# EEZ_AUX_PS_r4B40.net
KiCad netlist of a schematic drawn in EAGLE
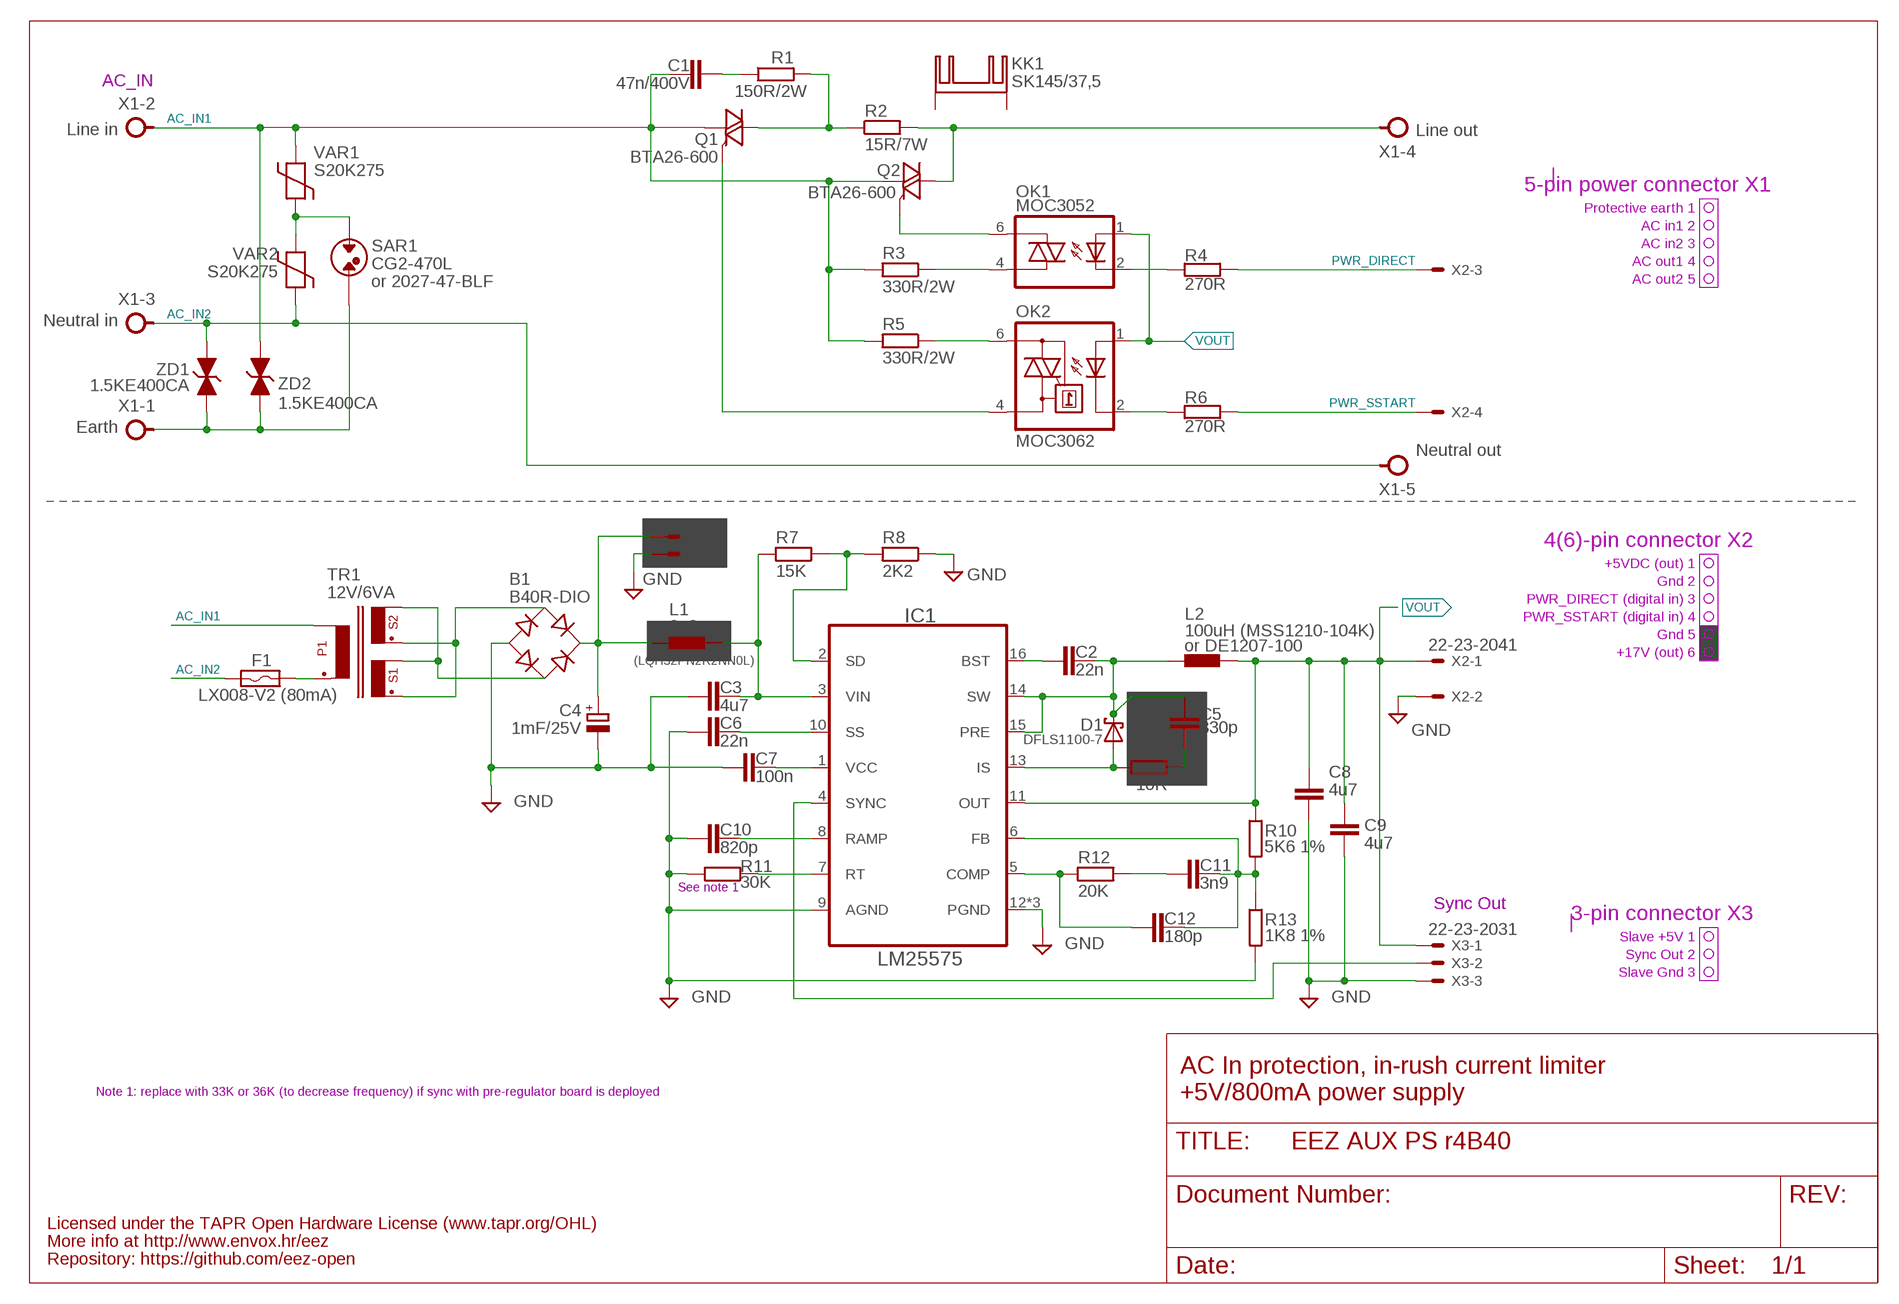
[diagram p0: schematic, sheet 1]

(export (version "E")
  (design (tool "Eeschema 10.0.6"))
  (components
    (comp (ref "B1")
      (value "B40R-DIO")
      (footprint "eagle-import:RB1A")
      (libsource (lib "eagle-import") (part "RECTIFIER-RB1A"))
    )
    (comp (ref "C1")
      (value "47n/400V")
      (footprint "eagle-import:C075-052X106")
      (libsource (lib "eagle-import") (part "C-EU075-052X106"))
    )
    (comp (ref "C2")
      (value "22n")
      (footprint "eagle-import:C0805")
      (libsource (lib "eagle-import") (part "C-EUC0805"))
    )
    (comp (ref "C3")
      (value "4u7")
      (footprint "eagle-import:C1210")
      (libsource (lib "eagle-import") (part "C-EUC1210"))
    )
    (comp (ref "C4")
      (value "1mF/25V")
      (footprint "eagle-import:ECAP5_10.5")
      (libsource (lib "eagle-import") (part "ECAP5G_10.5MM"))
    )
    (comp (ref "C5")
      (value "330p")
      (footprint "eagle-import:C0805")
      (libsource (lib "eagle-import") (part "C-EUC0805"))
    )
    (comp (ref "C6")
      (value "22n")
      (footprint "eagle-import:C0805")
      (libsource (lib "eagle-import") (part "C-EUC0805"))
    )
    (comp (ref "C7")
      (value "100n")
      (footprint "eagle-import:C0805")
      (libsource (lib "eagle-import") (part "C-EUC0805"))
    )
    (comp (ref "C8")
      (value "4u7")
      (footprint "eagle-import:C1210")
      (libsource (lib "eagle-import") (part "C-EUC1210"))
    )
    (comp (ref "C9")
      (value "4u7")
      (footprint "eagle-import:C1210")
      (libsource (lib "eagle-import") (part "C-EUC1210"))
    )
    (comp (ref "C10")
      (value "820p")
      (footprint "eagle-import:C0805")
      (libsource (lib "eagle-import") (part "C-EUC0805"))
    )
    (comp (ref "C11")
      (value "3n9")
      (footprint "eagle-import:C0805")
      (libsource (lib "eagle-import") (part "C-EUC0805"))
    )
    (comp (ref "C12")
      (value "180p")
      (footprint "eagle-import:C0805")
      (libsource (lib "eagle-import") (part "C-EUC0805"))
    )
    (comp (ref "D1")
      (value "DFLS1100-7")
      (footprint "eagle-import:SOD123")
      (libsource (lib "eagle-import") (part "SCHOTTKYSOD123"))
    )
    (comp (ref "F1")
      (value "LX008-V2 (80mA)")
      (footprint "eagle-import:POLYSWITCH-R7")
      (libsource (lib "eagle-import") (part "FUSE_RESETTABLER7"))
    )
    (comp (ref "IC1")
      (value "LM25575")
      (footprint "eagle-import:SOP65P640X110-17N_HOLE")
      (libsource (lib "eagle-import") (part "LM(2)5575"))
    )
    (comp (ref "KK1")
      (value "SK145/37,5")
      (footprint "eagle-import:SK145")
      (libsource (lib "eagle-import") (part "SK145"))
    )
    (comp (ref "L1")
      (value "2u2")
      (footprint "eagle-import:L1210")
      (libsource (lib "eagle-import") (part "L1210"))
    )
    (comp (ref "L2")
      (value "100uH (MSS1210-104K)")
      (footprint "eagle-import:MSS1278")
      (libsource (lib "eagle-import") (part "COILCRAFT_MSS1278"))
    )
    (comp (ref "OK1")
      (value "MOC3052")
      (footprint "eagle-import:DIL6-SMD")
      (libsource (lib "eagle-import") (part "MOC305X"))
    )
    (comp (ref "OK2")
      (value "MOC3062")
      (footprint "eagle-import:DIL6-SMD")
      (fields
        (field (name "MF") "FAIRCHILD SEMICONDUCTOR")
        (field (name "MPN") "MOC3033S-M")
        (field (name "MF_1") "FAIRCHILD SEMICONDUCTOR")
        (field (name "MPN_1") "MOC3033S-M")
        (field (name "OC_FARNELL") "unknown")
        (field (name "OC_NEWARK") "05C2878")
      )
      (libsource (lib "eagle-import") (part "MOC30S33"))
    )
    (comp (ref "Q1")
      (value "BTA26-600")
      (footprint "eagle-import:TOP3S-1")
      (libsource (lib "eagle-import") (part "BTA26-V"))
    )
    (comp (ref "Q2")
      (value "BTA26-600")
      (footprint "eagle-import:TOP3S-1")
      (libsource (lib "eagle-import") (part "BTA26-V"))
    )
    (comp (ref "R1")
      (value "150R/2W")
      (footprint "eagle-import:R2512")
      (libsource (lib "eagle-import") (part "R-EU_R2512"))
    )
    (comp (ref "R2")
      (value "15R/7W")
      (footprint "eagle-import:R_0913")
      (libsource (lib "eagle-import") (part "R_EU7W"))
    )
    (comp (ref "R3")
      (value "330R/2W")
      (footprint "eagle-import:R2512")
      (libsource (lib "eagle-import") (part "R-EU_R2512"))
    )
    (comp (ref "R4")
      (value "270R")
      (footprint "eagle-import:R0805")
      (libsource (lib "eagle-import") (part "R-EU_R0805"))
    )
    (comp (ref "R5")
      (value "330R/2W")
      (footprint "eagle-import:R2512")
      (libsource (lib "eagle-import") (part "R-EU_R2512"))
    )
    (comp (ref "R6")
      (value "270R")
      (footprint "eagle-import:R0805")
      (libsource (lib "eagle-import") (part "R-EU_R0805"))
    )
    (comp (ref "R7")
      (value "15K")
      (footprint "eagle-import:R0805")
      (libsource (lib "eagle-import") (part "R-EU_R0805"))
    )
    (comp (ref "R8")
      (value "2K2")
      (footprint "eagle-import:R0805")
      (libsource (lib "eagle-import") (part "R-EU_R0805"))
    )
    (comp (ref "R9")
      (value "10R")
      (footprint "eagle-import:R1206")
      (libsource (lib "eagle-import") (part "R-EU_R1206"))
    )
    (comp (ref "R10")
      (value "5K6 1%")
      (footprint "eagle-import:R0805")
      (libsource (lib "eagle-import") (part "R-EU_R0805"))
    )
    (comp (ref "R11")
      (value "30K")
      (footprint "eagle-import:R0805")
      (libsource (lib "eagle-import") (part "R-EU_R0805"))
    )
    (comp (ref "R12")
      (value "20K")
      (footprint "eagle-import:R0805")
      (libsource (lib "eagle-import") (part "R-EU_R0805"))
    )
    (comp (ref "R13")
      (value "1K8 1%")
      (footprint "eagle-import:R0805")
      (libsource (lib "eagle-import") (part "R-EU_R0805"))
    )
    (comp (ref "SAR1")
      (value "CG2-470L")
      (footprint "eagle-import:SAR")
      (libsource (lib "eagle-import") (part "SAR"))
    )
    (comp (ref "TR1")
      (value "12V/6VA")
      (footprint "eagle-import:PCB_TRAFO6VA_DUAL")
      (libsource (lib "eagle-import") (part "PCB_TRAFO6VACOMBO"))
    )
    (comp (ref "VAR1")
      (value "S20K275")
      (footprint "eagle-import:VARISTOR")
      (libsource (lib "eagle-import") (part "VARISTOR"))
    )
    (comp (ref "VAR2")
      (value "S20K275")
      (footprint "eagle-import:VARISTOR")
      (libsource (lib "eagle-import") (part "VARISTOR"))
    )
    (comp (ref "X1")
      (value "AC_IN")
      (footprint "eagle-import:TBLOCK5.0_5")
      (libsource (lib "eagle-import") (part "TBLOCK5.0_5A"))
    )
    (comp (ref "X2")
      (value "22-23-2041")
      (footprint "eagle-import:22-23-2061")
      (fields
        (field (name "MF") "MOLEX")
        (field (name "MPN") "22-23-2061")
        (field (name "MPN_1") "22-23-2061")
        (field (name "OC_FARNELL") "1462922")
        (field (name "OC_NEWARK") "27C1933")
      )
      (libsource (lib "eagle-import") (part "22-23-2061"))
    )
    (comp (ref "X3")
      (value "22-23-2031")
      (footprint "eagle-import:22-23-2031")
      (fields (field (name "MF") "MOLEX"))
      (libsource (lib "eagle-import") (part "22-23-2031"))
    )
    (comp (ref "ZD1")
      (value "1.5KE400CA")
      (footprint "eagle-import:DO201-BIDIR")
      (libsource (lib "eagle-import") (part "1.5KE-BIDIR"))
    )
    (comp (ref "ZD2")
      (value "1.5KE400CA")
      (footprint "eagle-import:DO201-BIDIR")
      (libsource (lib "eagle-import") (part "1.5KE-BIDIR"))
    )
  )
  (nets
    (net (code "1") (name "/AC_IN1") (class "Default")
      (node (ref "C1") (pin "2") (pinfunction "2_2") (pintype "passive"))
      (node (ref "Q1") (pin "A1") (pinfunction "A1_A1") (pintype "passive"))
      (node (ref "Q2") (pin "A1") (pinfunction "A1_A1") (pintype "passive"))
      (node (ref "R3") (pin "2") (pinfunction "2_2") (pintype "passive"))
      (node (ref "R5") (pin "2") (pinfunction "2_2") (pintype "passive"))
      (node (ref "TR1") (pin "NC1") (pinfunction "P1_NC1") (pintype "passive"))
      (node (ref "TR1") (pin "P1") (pinfunction "P1_P1") (pintype "passive"))
      (node (ref "TR1") (pin "P1.1") (pinfunction "P1_P1.1") (pintype "passive"))
      (node (ref "TR1") (pin "P1.2") (pinfunction "P1_P1.2") (pintype "passive"))
      (node (ref "VAR1") (pin "P$2") (pinfunction "P$2_P$2") (pintype "bidirectional"))
      (node (ref "X1") (pin "2") (pinfunction "1_2") (pintype "bidirectional"))
      (node (ref "ZD2") (pin "A") (pinfunction "2_A") (pintype "passive"))
    )
    (net (code "2") (name "/AC_IN2") (class "Default")
      (node (ref "F1") (pin "P$1") (pinfunction "1_P$1") (pintype "passive"))
      (node (ref "VAR2") (pin "P$1") (pinfunction "P$1_P$1") (pintype "bidirectional"))
      (node (ref "X1") (pin "3") (pinfunction "1_3") (pintype "bidirectional"))
      (node (ref "X1") (pin "5") (pinfunction "1_5") (pintype "bidirectional"))
      (node (ref "ZD1") (pin "A") (pinfunction "2_A") (pintype "passive"))
    )
    (net (code "3") (name "/PWR_DIRECT") (class "Default")
      (node (ref "R4") (pin "2") (pinfunction "2_2") (pintype "passive"))
      (node (ref "X2") (pin "3") (pinfunction "S_3") (pintype "passive"))
    )
    (net (code "4") (name "/PWR_SSTART") (class "Default")
      (node (ref "R6") (pin "2") (pinfunction "2_2") (pintype "passive"))
      (node (ref "X2") (pin "4") (pinfunction "S_4") (pintype "passive"))
    )
    (net (code "5") (name "GND") (class "Default")
      (node (ref "B1") (pin "-") (pinfunction "-_-") (pintype "passive"))
      (node (ref "C10") (pin "1") (pinfunction "1_1") (pintype "passive"))
      (node (ref "C3") (pin "2") (pinfunction "2_2") (pintype "passive"))
      (node (ref "C4") (pin "-") (pinfunction "-_-") (pintype "passive"))
      (node (ref "C6") (pin "2") (pinfunction "2_2") (pintype "passive"))
      (node (ref "C7") (pin "1") (pinfunction "1_1") (pintype "passive"))
      (node (ref "C8") (pin "2") (pinfunction "2_2") (pintype "passive"))
      (node (ref "C9") (pin "2") (pinfunction "2_2") (pintype "passive"))
      (node (ref "IC1") (pin "12") (pinfunction "PGND_12") (pintype "passive"))
      (node (ref "IC1") (pin "9") (pinfunction "AGND_9") (pintype "passive"))
      (node (ref "IC1") (pin "TP") (pinfunction "PGND_TP") (pintype "passive"))
      (node (ref "IC1") (pin "TP2") (pinfunction "PGND_TP2") (pintype "passive"))
      (node (ref "R11") (pin "2") (pinfunction "2_2") (pintype "passive"))
      (node (ref "R13") (pin "2") (pinfunction "2_2") (pintype "passive"))
      (node (ref "R8") (pin "1") (pinfunction "1_1") (pintype "passive"))
      (node (ref "X2") (pin "2") (pinfunction "S_2") (pintype "passive"))
      (node (ref "X2") (pin "5") (pinfunction "S_5") (pintype "passive"))
      (node (ref "X3") (pin "3") (pinfunction "S_3") (pintype "passive"))
    )
    (net (code "6") (name "Net-(B1-PadAC1)") (class "Default")
      (node (ref "B1") (pin "AC1") (pinfunction "AC1_AC1") (pintype "passive"))
      (node (ref "TR1") (pin "S1.1") (pinfunction "S1.1_S1.1") (pintype "passive"))
      (node (ref "TR1") (pin "S2.1") (pinfunction "S2.1_S2.1") (pintype "passive"))
      (node (ref "TR1") (pin "S2.1A") (pinfunction "S2.1_S2.1A") (pintype "passive"))
    )
    (net (code "7") (name "Net-(B1-PadAC2)") (class "Default")
      (node (ref "B1") (pin "AC2") (pinfunction "AC2_AC2") (pintype "passive"))
      (node (ref "TR1") (pin "S1.2") (pinfunction "S1.2_S1.2") (pintype "passive"))
      (node (ref "TR1") (pin "S1.2A") (pinfunction "S1.2_S1.2A") (pintype "passive"))
      (node (ref "TR1") (pin "S1.2NC") (pinfunction "S1.2_S1.2NC") (pintype "passive"))
      (node (ref "TR1") (pin "S2.2") (pinfunction "S2.2_S2.2") (pintype "passive"))
    )
    (net (code "8") (name "Net-(C1-Pad1)") (class "Default")
      (node (ref "C1") (pin "1") (pinfunction "1_1") (pintype "passive"))
      (node (ref "R1") (pin "1") (pinfunction "1_1") (pintype "passive"))
    )
    (net (code "9") (name "Net-(C5-Pad2)") (class "Default")
      (node (ref "C5") (pin "2") (pinfunction "2_2") (pintype "passive"))
      (node (ref "R9") (pin "2") (pinfunction "2_2") (pintype "passive"))
    )
    (net (code "10") (name "Net-(C11-Pad2)") (class "Default")
      (node (ref "C11") (pin "2") (pinfunction "2_2") (pintype "passive"))
      (node (ref "R12") (pin "2") (pinfunction "2_2") (pintype "passive"))
    )
    (net (code "11") (name "Net-(F1-2)") (class "Default")
      (node (ref "F1") (pin "P$2") (pinfunction "2_P$2") (pintype "passive"))
      (node (ref "TR1") (pin "P2") (pinfunction "P2_P2") (pintype "passive"))
      (node (ref "TR1") (pin "P2.1") (pinfunction "P2_P2.1") (pintype "passive"))
      (node (ref "TR1") (pin "P2.2") (pinfunction "P2_P2.2") (pintype "passive"))
    )
    (net (code "12") (name "Net-(IC1-BST)") (class "Default")
      (node (ref "C2") (pin "2") (pinfunction "2_2") (pintype "passive"))
      (node (ref "IC1") (pin "16") (pinfunction "BST_16") (pintype "input"))
    )
    (net (code "13") (name "Net-(IC1-COMP)") (class "Default")
      (node (ref "C12") (pin "2") (pinfunction "2_2") (pintype "passive"))
      (node (ref "IC1") (pin "5") (pinfunction "COMP_5") (pintype "input"))
      (node (ref "R12") (pin "1") (pinfunction "1_1") (pintype "passive"))
    )
    (net (code "14") (name "Net-(IC1-FB)") (class "Default")
      (node (ref "C11") (pin "1") (pinfunction "1_1") (pintype "passive"))
      (node (ref "C12") (pin "1") (pinfunction "1_1") (pintype "passive"))
      (node (ref "IC1") (pin "6") (pinfunction "FB_6") (pintype "input"))
      (node (ref "R10") (pin "2") (pinfunction "2_2") (pintype "passive"))
      (node (ref "R13") (pin "1") (pinfunction "1_1") (pintype "passive"))
    )
    (net (code "15") (name "Net-(IC1-IS)") (class "Default")
      (node (ref "D1") (pin "A") (pinfunction "A_A") (pintype "passive"))
      (node (ref "IC1") (pin "13") (pinfunction "IS_13") (pintype "input"))
      (node (ref "R9") (pin "1") (pinfunction "1_1") (pintype "passive"))
    )
    (net (code "16") (name "Net-(IC1-PRE)") (class "Default")
      (node (ref "C2") (pin "1") (pinfunction "1_1") (pintype "passive"))
      (node (ref "C5") (pin "1") (pinfunction "1_1") (pintype "passive"))
      (node (ref "D1") (pin "C") (pinfunction "C_C") (pintype "passive"))
      (node (ref "IC1") (pin "14") (pinfunction "SW_14") (pintype "output"))
      (node (ref "IC1") (pin "15") (pinfunction "PRE_15") (pintype "input"))
      (node (ref "L2") (pin "1") (pinfunction "1_1") (pintype "passive"))
    )
    (net (code "17") (name "Net-(IC1-RAMP)") (class "Default")
      (node (ref "C10") (pin "2") (pinfunction "2_2") (pintype "passive"))
      (node (ref "IC1") (pin "8") (pinfunction "RAMP_8") (pintype "input"))
    )
    (net (code "18") (name "Net-(IC1-RT)") (class "Default")
      (node (ref "IC1") (pin "7") (pinfunction "RT_7") (pintype "input"))
      (node (ref "R11") (pin "1") (pinfunction "1_1") (pintype "passive"))
    )
    (net (code "19") (name "Net-(IC1-SD)") (class "Default")
      (node (ref "IC1") (pin "2") (pinfunction "SD_2") (pintype "input"))
      (node (ref "R7") (pin "1") (pinfunction "1_1") (pintype "passive"))
      (node (ref "R8") (pin "2") (pinfunction "2_2") (pintype "passive"))
    )
    (net (code "20") (name "Net-(IC1-SS)") (class "Default")
      (node (ref "C6") (pin "1") (pinfunction "1_1") (pintype "passive"))
      (node (ref "IC1") (pin "10") (pinfunction "SS_10") (pintype "input"))
    )
    (net (code "21") (name "Net-(IC1-SYNC)") (class "Default")
      (node (ref "IC1") (pin "4") (pinfunction "SYNC_4") (pintype "input"))
      (node (ref "X3") (pin "2") (pinfunction "S_2") (pintype "passive"))
    )
    (net (code "22") (name "Net-(IC1-VCC)") (class "Default")
      (node (ref "C7") (pin "2") (pinfunction "2_2") (pintype "passive"))
      (node (ref "IC1") (pin "1") (pinfunction "VCC_1") (pintype "power_in"))
    )
    (net (code "23") (name "Net-(IC1-VIN)") (class "Default")
      (node (ref "C3") (pin "1") (pinfunction "1_1") (pintype "passive"))
      (node (ref "IC1") (pin "3") (pinfunction "VIN_3") (pintype "input"))
      (node (ref "L1") (pin "2") (pinfunction "2_2") (pintype "passive"))
      (node (ref "R7") (pin "2") (pinfunction "2_2") (pintype "passive"))
    )
    (net (code "24") (name "Net-(OK1-A1)") (class "Default")
      (node (ref "OK1") (pin "4") (pinfunction "A1_4") (pintype "passive"))
      (node (ref "R3") (pin "1") (pinfunction "1_1") (pintype "passive"))
    )
    (net (code "25") (name "Net-(OK1-A2)") (class "Default")
      (node (ref "OK1") (pin "6") (pinfunction "A2_6") (pintype "passive"))
      (node (ref "Q2") (pin "G") (pinfunction "G_G") (pintype "passive"))
    )
    (net (code "26") (name "Net-(OK1-C)") (class "Default")
      (node (ref "OK1") (pin "2") (pinfunction "C_2") (pintype "passive"))
      (node (ref "R4") (pin "1") (pinfunction "1_1") (pintype "passive"))
    )
    (net (code "27") (name "Net-(OK2-A1)") (class "Default")
      (node (ref "OK2") (pin "4") (pinfunction "A1_4") (pintype "passive"))
      (node (ref "Q1") (pin "G") (pinfunction "G_G") (pintype "passive"))
    )
    (net (code "28") (name "Net-(OK2-A2)") (class "Default")
      (node (ref "OK2") (pin "6") (pinfunction "A2_6") (pintype "passive"))
      (node (ref "R5") (pin "1") (pinfunction "1_1") (pintype "passive"))
    )
    (net (code "29") (name "Net-(OK2-C)") (class "Default")
      (node (ref "OK2") (pin "2") (pinfunction "C_2") (pintype "passive"))
      (node (ref "R6") (pin "1") (pinfunction "1_1") (pintype "passive"))
    )
    (net (code "30") (name "Net-(Q1-PadA2)") (class "Default")
      (node (ref "Q1") (pin "A2") (pinfunction "A2_A2") (pintype "passive"))
      (node (ref "R1") (pin "2") (pinfunction "2_2") (pintype "passive"))
      (node (ref "R2") (pin "1") (pinfunction "1_1") (pintype "passive"))
    )
    (net (code "31") (name "Net-(SAR1-PadP$1)") (class "Default")
      (node (ref "SAR1") (pin "P$1") (pinfunction "P$1_P$1") (pintype "bidirectional"))
      (node (ref "VAR1") (pin "P$1") (pinfunction "P$1_P$1") (pintype "bidirectional"))
      (node (ref "VAR2") (pin "P$2") (pinfunction "P$2_P$2") (pintype "bidirectional"))
    )
    (net (code "32") (name "Net-(X1D-1)") (class "Default")
      (node (ref "Q2") (pin "A2") (pinfunction "A2_A2") (pintype "passive"))
      (node (ref "R2") (pin "2") (pinfunction "2_2") (pintype "passive"))
      (node (ref "X1") (pin "4") (pinfunction "1_4") (pintype "bidirectional"))
    )
    (net (code "33") (name "Net-(X2F-S)") (class "Default")
      (node (ref "B1") (pin "+") (pinfunction "+_+") (pintype "passive"))
      (node (ref "C4") (pin "+") (pinfunction "+_+") (pintype "passive"))
      (node (ref "L1") (pin "1") (pinfunction "1_1") (pintype "passive"))
      (node (ref "X2") (pin "6") (pinfunction "S_6") (pintype "passive"))
    )
    (net (code "34") (name "Net-(ZD1-1)") (class "Default")
      (node (ref "SAR1") (pin "P$2") (pinfunction "P$2_P$2") (pintype "bidirectional"))
      (node (ref "X1") (pin "1") (pinfunction "1_1") (pintype "bidirectional"))
      (node (ref "ZD1") (pin "C") (pinfunction "1_C") (pintype "passive"))
      (node (ref "ZD2") (pin "C") (pinfunction "1_C") (pintype "passive"))
    )
    (net (code "35") (name "VOUT") (class "Default")
      (node (ref "C8") (pin "1") (pinfunction "1_1") (pintype "passive"))
      (node (ref "C9") (pin "1") (pinfunction "1_1") (pintype "passive"))
      (node (ref "IC1") (pin "11") (pinfunction "OUT_11") (pintype "output"))
      (node (ref "L2") (pin "2") (pinfunction "2_2") (pintype "passive"))
      (node (ref "OK1") (pin "1") (pinfunction "A_1") (pintype "passive"))
      (node (ref "OK2") (pin "1") (pinfunction "A_1") (pintype "passive"))
      (node (ref "R10") (pin "1") (pinfunction "1_1") (pintype "passive"))
      (node (ref "X2") (pin "1") (pinfunction "S_1") (pintype "passive"))
      (node (ref "X3") (pin "1") (pinfunction "S_1") (pintype "passive"))
    )
    (net (code "36") (name "unconnected-(KK1-K-Pad1)") (class "Default")
      (node (ref "KK1") (pin "1") (pinfunction "K_1") (pintype "passive"))
    )
    (net (code "37") (name "unconnected-(KK1-K-Pad2)") (class "Default")
      (node (ref "KK1") (pin "2") (pinfunction "K_2") (pintype "passive"))
    )
  )
)
